# h_bridge.net
KiCad netlist of a schematic drawn in EAGLE
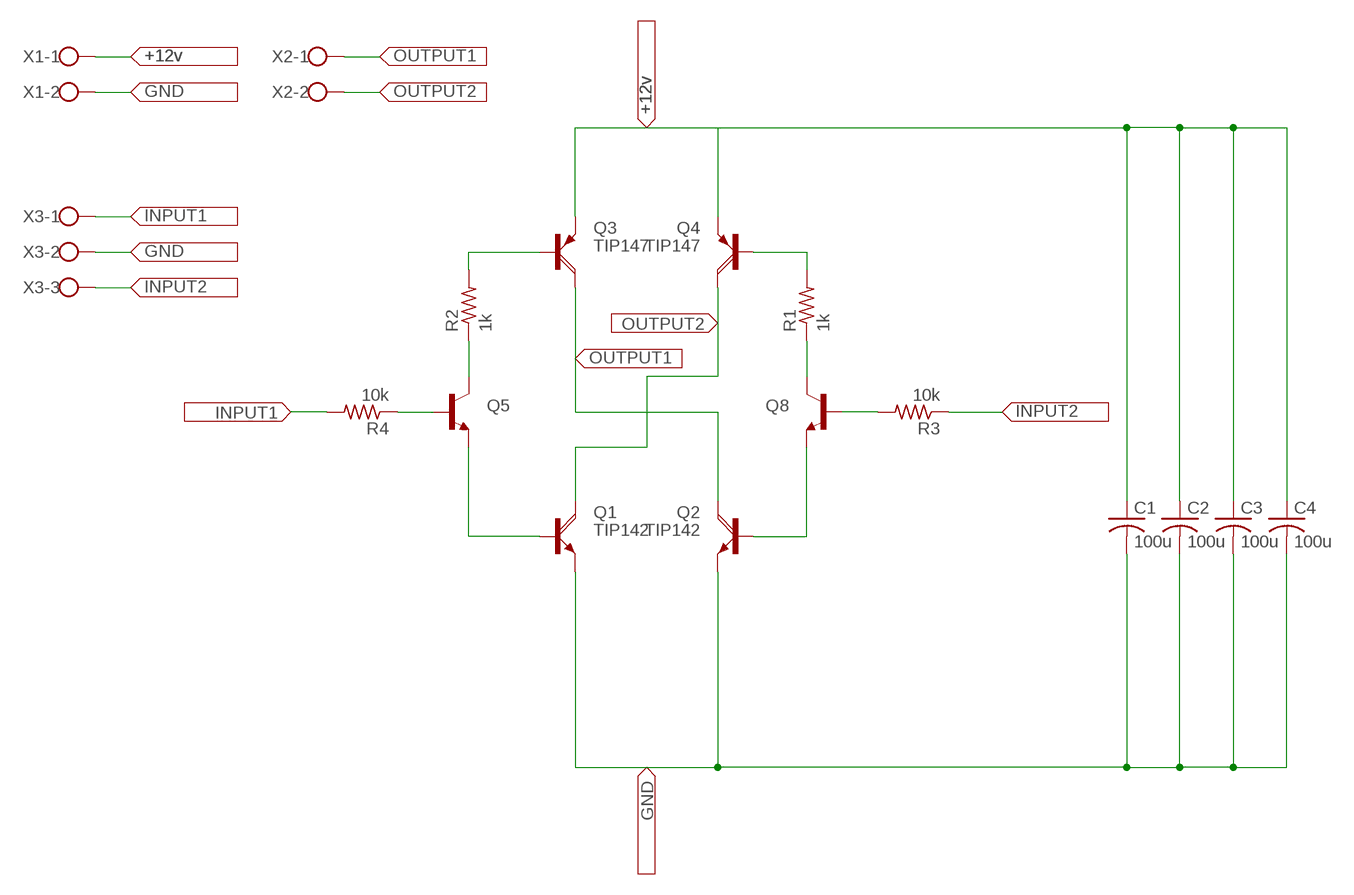
[diagram p0: schematic, sheet 1]

(export (version "E")
  (design (tool "Eeschema 10.0.6"))
  (components
    (comp (ref "C1")
      (value "100u")
      (footprint "eagle-import:C025-025X050")
      (libsource (lib "eagle-import") (part "C-US025-025X050"))
    )
    (comp (ref "C2")
      (value "100u")
      (footprint "eagle-import:C025-025X050")
      (libsource (lib "eagle-import") (part "C-US025-025X050"))
    )
    (comp (ref "C3")
      (value "100u")
      (footprint "eagle-import:C025-025X050")
      (libsource (lib "eagle-import") (part "C-US025-025X050"))
    )
    (comp (ref "C4")
      (value "100u")
      (footprint "eagle-import:C025-025X050")
      (libsource (lib "eagle-import") (part "C-US025-025X050"))
    )
    (comp (ref "Q1")
      (value "TIP142")
      (footprint "eagle-import:SOT93")
      (libsource (lib "eagle-import") (part "TIP142"))
    )
    (comp (ref "Q2")
      (value "TIP142")
      (footprint "eagle-import:SOT93")
      (libsource (lib "eagle-import") (part "TIP142"))
    )
    (comp (ref "Q3")
      (value "TIP147")
      (footprint "eagle-import:SOT93")
      (libsource (lib "eagle-import") (part "TIP147"))
    )
    (comp (ref "Q4")
      (value "TIP147")
      (footprint "eagle-import:SOT93")
      (libsource (lib "eagle-import") (part "TIP147"))
    )
    (comp (ref "Q5")
      (value "TRANSISTOR_NPNTO92")
      (footprint "eagle-import:TO-92")
      (libsource (lib "eagle-import") (part "TRANSISTOR_NPNTO92"))
    )
    (comp (ref "Q8")
      (value "TRANSISTOR_NPNTO92")
      (footprint "eagle-import:TO-92")
      (libsource (lib "eagle-import") (part "TRANSISTOR_NPNTO92"))
    )
    (comp (ref "R1")
      (value "1k")
      (footprint "eagle-import:0207_15")
      (libsource (lib "eagle-import") (part "R-US_0207/15"))
    )
    (comp (ref "R2")
      (value "1k")
      (footprint "eagle-import:0207_15")
      (libsource (lib "eagle-import") (part "R-US_0207/15"))
    )
    (comp (ref "R3")
      (value "10k")
      (footprint "eagle-import:0207_15")
      (libsource (lib "eagle-import") (part "R-US_0207/15"))
    )
    (comp (ref "R4")
      (value "10k")
      (footprint "eagle-import:0207_15")
      (libsource (lib "eagle-import") (part "R-US_0207/15"))
    )
    (comp (ref "X1")
      (value "W237-02P")
      (footprint "eagle-import:W237-132")
      (libsource (lib "eagle-import") (part "W237-02P"))
    )
    (comp (ref "X2")
      (value "W237-02P")
      (footprint "eagle-import:W237-132")
      (libsource (lib "eagle-import") (part "W237-02P"))
    )
    (comp (ref "X3")
      (value "W237-03P")
      (footprint "eagle-import:W237-133")
      (libsource (lib "eagle-import") (part "W237-03P"))
    )
  )
  (nets
    (net (code "1") (name "/+12V") (class "Default")
      (node (ref "C1") (pin "1") (pinfunction "1_1") (pintype "passive"))
      (node (ref "C2") (pin "1") (pinfunction "1_1") (pintype "passive"))
      (node (ref "C3") (pin "1") (pinfunction "1_1") (pintype "passive"))
      (node (ref "C4") (pin "1") (pinfunction "1_1") (pintype "passive"))
      (node (ref "Q3") (pin "E") (pinfunction "E_E") (pintype "passive"))
      (node (ref "Q4") (pin "E") (pinfunction "E_E") (pintype "passive"))
      (node (ref "X1") (pin "1") (pinfunction "KL_1") (pintype "passive"))
    )
    (net (code "2") (name "/GND") (class "Default")
      (node (ref "C1") (pin "2") (pinfunction "2_2") (pintype "passive"))
      (node (ref "C2") (pin "2") (pinfunction "2_2") (pintype "passive"))
      (node (ref "C3") (pin "2") (pinfunction "2_2") (pintype "passive"))
      (node (ref "C4") (pin "2") (pinfunction "2_2") (pintype "passive"))
      (node (ref "Q1") (pin "E") (pinfunction "E_E") (pintype "passive"))
      (node (ref "Q2") (pin "E") (pinfunction "E_E") (pintype "passive"))
      (node (ref "X1") (pin "2") (pinfunction "KL_2") (pintype "passive"))
      (node (ref "X3") (pin "2") (pinfunction "KL_2") (pintype "passive"))
    )
    (net (code "3") (name "/INPUT1") (class "Default")
      (node (ref "R4") (pin "2") (pinfunction "2_2") (pintype "passive"))
      (node (ref "X3") (pin "1") (pinfunction "KL_1") (pintype "passive"))
    )
    (net (code "4") (name "/INPUT2") (class "Default")
      (node (ref "R3") (pin "1") (pinfunction "1_1") (pintype "passive"))
      (node (ref "X3") (pin "3") (pinfunction "KL_3") (pintype "passive"))
    )
    (net (code "5") (name "/OUTPUT1") (class "Default")
      (node (ref "Q2") (pin "C") (pinfunction "C_C") (pintype "passive"))
      (node (ref "Q3") (pin "C") (pinfunction "C_C") (pintype "passive"))
      (node (ref "X2") (pin "1") (pinfunction "KL_1") (pintype "passive"))
    )
    (net (code "6") (name "/OUTPUT2") (class "Default")
      (node (ref "Q1") (pin "C") (pinfunction "C_C") (pintype "passive"))
      (node (ref "Q4") (pin "C") (pinfunction "C_C") (pintype "passive"))
      (node (ref "X2") (pin "2") (pinfunction "KL_2") (pintype "passive"))
    )
    (net (code "7") (name "Net-(Q3-PadB)") (class "Default")
      (node (ref "Q3") (pin "B") (pinfunction "B_B") (pintype "passive"))
      (node (ref "R2") (pin "2") (pinfunction "2_2") (pintype "passive"))
    )
    (net (code "8") (name "Net-(Q4-PadB)") (class "Default")
      (node (ref "Q4") (pin "B") (pinfunction "B_B") (pintype "passive"))
      (node (ref "R1") (pin "2") (pinfunction "2_2") (pintype "passive"))
    )
    (net (code "9") (name "Net-(Q5-B)") (class "Default")
      (node (ref "Q5") (pin "2") (pinfunction "B_2") (pintype "passive"))
      (node (ref "R4") (pin "1") (pinfunction "1_1") (pintype "passive"))
    )
    (net (code "10") (name "Net-(Q5-C)") (class "Default")
      (node (ref "Q5") (pin "3") (pinfunction "C_3") (pintype "passive"))
      (node (ref "R2") (pin "1") (pinfunction "1_1") (pintype "passive"))
    )
    (net (code "11") (name "Net-(Q5-E)") (class "Default")
      (node (ref "Q1") (pin "B") (pinfunction "B_B") (pintype "passive"))
      (node (ref "Q5") (pin "1") (pinfunction "E_1") (pintype "passive"))
    )
    (net (code "12") (name "Net-(Q8-B)") (class "Default")
      (node (ref "Q8") (pin "2") (pinfunction "B_2") (pintype "passive"))
      (node (ref "R3") (pin "2") (pinfunction "2_2") (pintype "passive"))
    )
    (net (code "13") (name "Net-(Q8-C)") (class "Default")
      (node (ref "Q8") (pin "3") (pinfunction "C_3") (pintype "passive"))
      (node (ref "R1") (pin "1") (pinfunction "1_1") (pintype "passive"))
    )
    (net (code "14") (name "Net-(Q8-E)") (class "Default")
      (node (ref "Q2") (pin "B") (pinfunction "B_B") (pintype "passive"))
      (node (ref "Q8") (pin "1") (pinfunction "E_1") (pintype "passive"))
    )
  )
)
